# AdafruitUltimateGPS.net
KiCad netlist of a schematic drawn in EAGLE
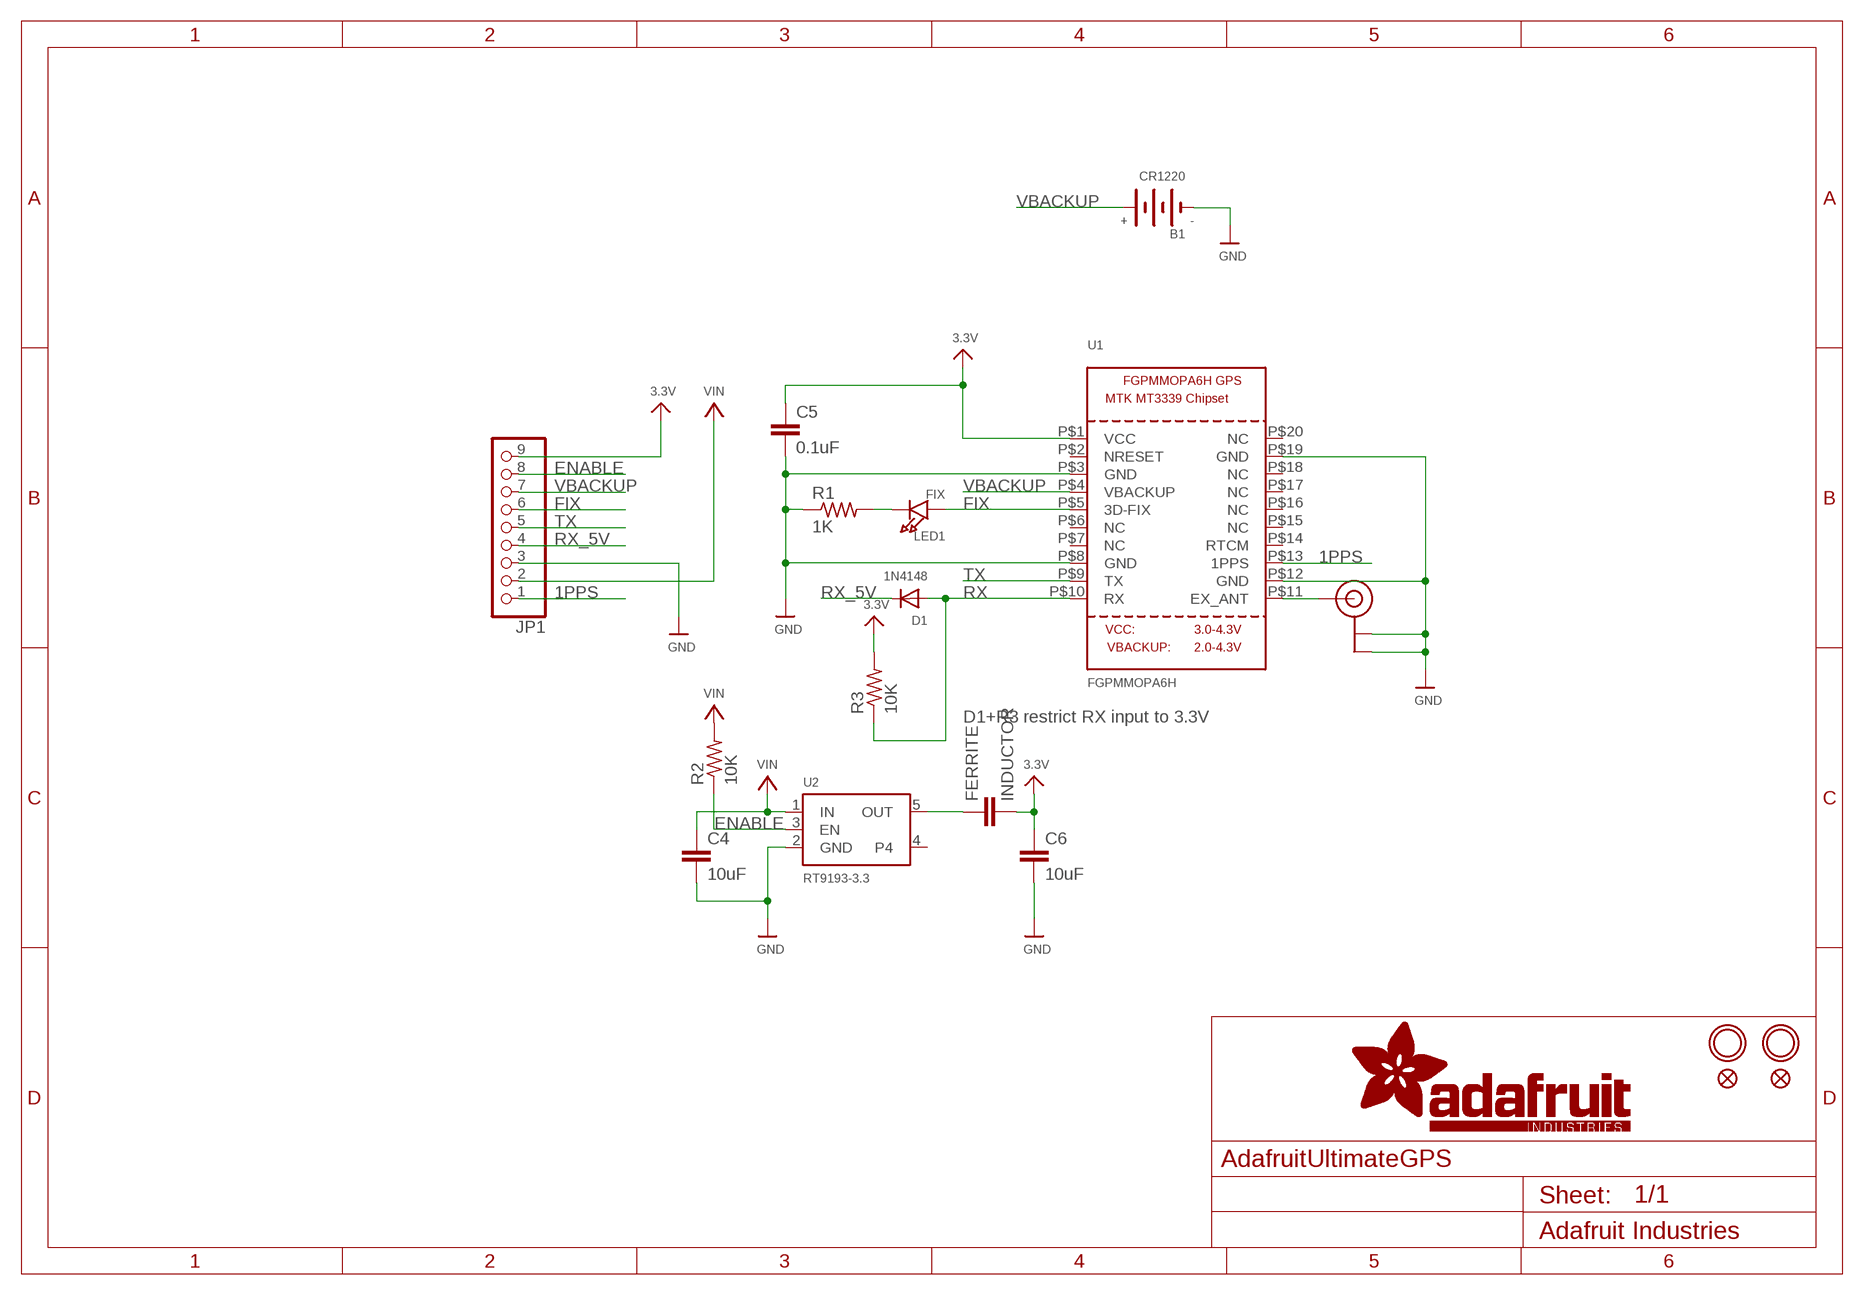
[diagram p0: schematic, sheet 1]

(export (version "E")
  (design (tool "Eeschema 10.0.6"))
  (components
    (comp (ref "B1")
      (value "CR1220")
      (footprint "eagle-import:CR1220")
      (libsource (lib "eagle-import") (part "BATTERYCR1220_SMT"))
    )
    (comp (ref "C4")
      (value "10uF")
      (footprint "eagle-import:C0603")
      (libsource (lib "eagle-import") (part "C-EUC0603"))
    )
    (comp (ref "C5")
      (value "0.1uF")
      (footprint "eagle-import:C0603")
      (libsource (lib "eagle-import") (part "C-EUC0603"))
    )
    (comp (ref "C6")
      (value "10uF")
      (footprint "eagle-import:C0603")
      (libsource (lib "eagle-import") (part "C-EUC0603"))
    )
    (comp (ref "D1")
      (value "1N4148")
      (footprint "eagle-import:SOD-323F")
      (libsource (lib "eagle-import") (part "DIODESOD-323F"))
    )
    (comp (ref "FERRITE")
      (value "INDUCTOR")
      (footprint "eagle-import:C0805")
      (libsource (lib "eagle-import") (part "C-EUC0805"))
    )
    (comp (ref "FID1")
      (value "FIDUCIAL\"\"")
      (footprint "eagle-import:FIDUCIAL_1MM")
      (libsource (lib "eagle-import") (part "FIDUCIAL{dblquote}{dblquote}"))
    )
    (comp (ref "FID2")
      (value "FIDUCIAL\"\"")
      (footprint "eagle-import:FIDUCIAL_1MM")
      (libsource (lib "eagle-import") (part "FIDUCIAL{dblquote}{dblquote}"))
    )
    (comp (ref "JP1")
      (value "HEADER-1X970MIL")
      (footprint "eagle-import:1X09_ROUND_70")
      (libsource (lib "eagle-import") (part "HEADER-1X970MIL"))
    )
    (comp (ref "LED1")
      (value "FIX")
      (footprint "eagle-import:CHIPLED_0805")
      (libsource (lib "eagle-import") (part "LED0805"))
    )
    (comp (ref "R1")
      (value "1K")
      (footprint "eagle-import:R0603")
      (libsource (lib "eagle-import") (part "R-US_R0603"))
    )
    (comp (ref "R2")
      (value "10K")
      (footprint "eagle-import:R0603")
      (libsource (lib "eagle-import") (part "R-US_R0603"))
    )
    (comp (ref "R3")
      (value "10K")
      (footprint "eagle-import:R0603")
      (libsource (lib "eagle-import") (part "R-US_R0603"))
    )
    (comp (ref "U$8")
      (value "MOUNTINGHOLE2.0")
      (footprint "eagle-import:MOUNTINGHOLE_2.0_PLATED")
      (libsource (lib "eagle-import") (part "MOUNTINGHOLE2.0"))
    )
    (comp (ref "U$9")
      (value "MOUNTINGHOLE2.0")
      (footprint "eagle-import:MOUNTINGHOLE_2.0_PLATED")
      (libsource (lib "eagle-import") (part "MOUNTINGHOLE2.0"))
    )
    (comp (ref "U$20")
      (value "U.FL")
      (footprint "eagle-import:U.FL")
      (libsource (lib "eagle-import") (part "U.FL"))
    )
    (comp (ref "U1")
      (value "FGPMMOPA6H")
      (footprint "eagle-import:FGPMMOPA6H")
      (libsource (lib "eagle-import") (part "GPS_FGPMMOPA6H"))
    )
    (comp (ref "U2")
      (value "RT9193-3.3")
      (footprint "eagle-import:SOT23-5")
      (libsource (lib "eagle-import") (part "VREG_SOT23-5"))
    )
  )
  (nets
    (net (code "1") (name "/1PPS") (class "Default")
      (node (ref "JP1") (pin "1") (pinfunction "1_1") (pintype "passive"))
      (node (ref "U1") (pin "P$13") (pinfunction "1PPS_P$13") (pintype "bidirectional"))
    )
    (net (code "2") (name "/ENABLE") (class "Default")
      (node (ref "JP1") (pin "8") (pinfunction "8_8") (pintype "passive"))
      (node (ref "R2") (pin "1") (pinfunction "1_1") (pintype "passive"))
      (node (ref "U2") (pin "3") (pinfunction "EN_3") (pintype "bidirectional"))
    )
    (net (code "3") (name "/FIX") (class "Default")
      (node (ref "JP1") (pin "6") (pinfunction "6_6") (pintype "passive"))
      (node (ref "LED1") (pin "A") (pinfunction "A_A") (pintype "passive"))
      (node (ref "U1") (pin "P$5") (pinfunction "3D-FIX_P$5") (pintype "bidirectional"))
    )
    (net (code "4") (name "/RX") (class "Default")
      (node (ref "D1") (pin "A") (pinfunction "A_A") (pintype "passive"))
      (node (ref "R3") (pin "1") (pinfunction "1_1") (pintype "passive"))
      (node (ref "U1") (pin "P$10") (pinfunction "RX_P$10") (pintype "bidirectional"))
    )
    (net (code "5") (name "/RX_5V") (class "Default")
      (node (ref "D1") (pin "C") (pinfunction "C_C") (pintype "passive"))
      (node (ref "JP1") (pin "4") (pinfunction "4_4") (pintype "passive"))
    )
    (net (code "6") (name "/TX") (class "Default")
      (node (ref "JP1") (pin "5") (pinfunction "5_5") (pintype "passive"))
      (node (ref "U1") (pin "P$9") (pinfunction "TX_P$9") (pintype "bidirectional"))
    )
    (net (code "7") (name "/VBACKUP") (class "Default")
      (node (ref "B1") (pin "+$1") (pinfunction "+_+$1") (pintype "passive"))
      (node (ref "JP1") (pin "7") (pinfunction "7_7") (pintype "passive"))
      (node (ref "U1") (pin "P$4") (pinfunction "VBACKUP_P$4") (pintype "bidirectional"))
    )
    (net (code "8") (name "3.3V") (class "Default")
      (node (ref "C5") (pin "1") (pinfunction "1_1") (pintype "passive"))
      (node (ref "C6") (pin "1") (pinfunction "1_1") (pintype "passive"))
      (node (ref "FERRITE") (pin "2") (pinfunction "2_2") (pintype "passive"))
      (node (ref "JP1") (pin "9") (pinfunction "9_9") (pintype "passive"))
      (node (ref "R3") (pin "2") (pinfunction "2_2") (pintype "passive"))
      (node (ref "U1") (pin "P$1") (pinfunction "VCC_P$1") (pintype "bidirectional"))
    )
    (net (code "9") (name "GND") (class "Default")
      (node (ref "B1") (pin "-") (pinfunction "-_-") (pintype "passive"))
      (node (ref "C4") (pin "2") (pinfunction "2_2") (pintype "passive"))
      (node (ref "C5") (pin "2") (pinfunction "2_2") (pintype "passive"))
      (node (ref "C6") (pin "2") (pinfunction "2_2") (pintype "passive"))
      (node (ref "JP1") (pin "3") (pinfunction "3_3") (pintype "passive"))
      (node (ref "R1") (pin "1") (pinfunction "1_1") (pintype "passive"))
      (node (ref "U$20") (pin "P$1") (pinfunction "GND_P$1") (pintype "bidirectional"))
      (node (ref "U$20") (pin "P$2") (pinfunction "GND_P$2") (pintype "bidirectional"))
      (node (ref "U1") (pin "P$12") (pinfunction "GND_P$12") (pintype "bidirectional"))
      (node (ref "U1") (pin "P$19") (pinfunction "GND_P$19") (pintype "bidirectional"))
      (node (ref "U1") (pin "P$3") (pinfunction "GND_P$3") (pintype "bidirectional"))
      (node (ref "U1") (pin "P$8") (pinfunction "GND_P$8") (pintype "bidirectional"))
      (node (ref "U2") (pin "2") (pinfunction "GND_2") (pintype "bidirectional"))
    )
    (net (code "10") (name "Net-(LED1-PadC)") (class "Default")
      (node (ref "LED1") (pin "C") (pinfunction "C_C") (pintype "passive"))
      (node (ref "R1") (pin "2") (pinfunction "2_2") (pintype "passive"))
    )
    (net (code "11") (name "Net-(U$20-SIGNAL)") (class "Default")
      (node (ref "U$20") (pin "P$3") (pinfunction "SIGNAL_P$3") (pintype "bidirectional"))
      (node (ref "U1") (pin "P$11") (pinfunction "EX_ANT_P$11") (pintype "bidirectional"))
    )
    (net (code "12") (name "Net-(U2-OUT)") (class "Default")
      (node (ref "FERRITE") (pin "1") (pinfunction "1_1") (pintype "passive"))
      (node (ref "U2") (pin "5") (pinfunction "OUT_5") (pintype "bidirectional"))
    )
    (net (code "13") (name "VIN") (class "Default")
      (node (ref "C4") (pin "1") (pinfunction "1_1") (pintype "passive"))
      (node (ref "JP1") (pin "2") (pinfunction "2_2") (pintype "passive"))
      (node (ref "R2") (pin "2") (pinfunction "2_2") (pintype "passive"))
      (node (ref "U2") (pin "1") (pinfunction "IN_1") (pintype "bidirectional"))
    )
    (net (code "14") (name "unconnected-(U1-NC-PadP$6)") (class "Default")
      (node (ref "U1") (pin "P$6") (pinfunction "NC_P$6") (pintype "bidirectional"))
    )
    (net (code "15") (name "unconnected-(U1-NC-PadP$7)") (class "Default")
      (node (ref "U1") (pin "P$7") (pinfunction "NC_P$7") (pintype "bidirectional"))
    )
    (net (code "16") (name "unconnected-(U1-NC-PadP$15)") (class "Default")
      (node (ref "U1") (pin "P$15") (pinfunction "NC_P$15") (pintype "bidirectional"))
    )
    (net (code "17") (name "unconnected-(U1-NC-PadP$16)") (class "Default")
      (node (ref "U1") (pin "P$16") (pinfunction "NC_P$16") (pintype "bidirectional"))
    )
    (net (code "18") (name "unconnected-(U1-NC-PadP$17)") (class "Default")
      (node (ref "U1") (pin "P$17") (pinfunction "NC_P$17") (pintype "bidirectional"))
    )
    (net (code "19") (name "unconnected-(U1-NC-PadP$18)") (class "Default")
      (node (ref "U1") (pin "P$18") (pinfunction "NC_P$18") (pintype "bidirectional"))
    )
    (net (code "20") (name "unconnected-(U1-NC-PadP$20)") (class "Default")
      (node (ref "U1") (pin "P$20") (pinfunction "NC_P$20") (pintype "bidirectional"))
    )
    (net (code "21") (name "unconnected-(U1-NRESET-PadP$2)") (class "Default")
      (node (ref "U1") (pin "P$2") (pinfunction "NRESET_P$2") (pintype "bidirectional"))
    )
    (net (code "22") (name "unconnected-(U1-RTCM-PadP$14)") (class "Default")
      (node (ref "U1") (pin "P$14") (pinfunction "RTCM_P$14") (pintype "bidirectional"))
    )
    (net (code "23") (name "unconnected-(U2-P4-Pad4)") (class "Default")
      (node (ref "U2") (pin "4") (pinfunction "P4_4") (pintype "bidirectional"))
    )
  )
)
